# motor_driver.net
KiCad netlist of a schematic drawn in Altium Designer
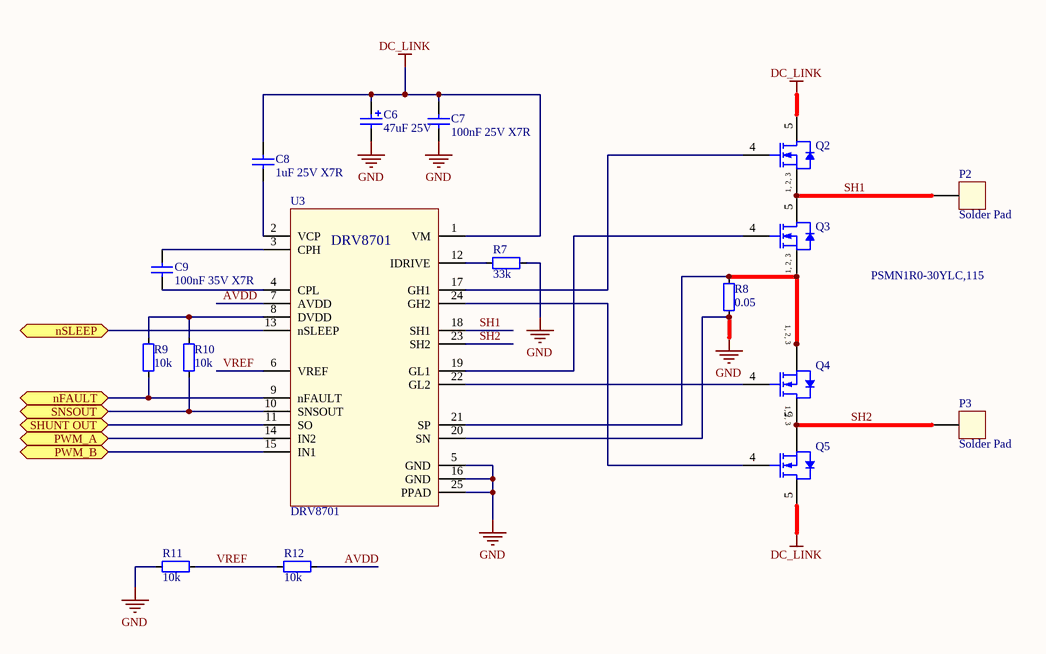
[diagram p0: motor driver.SchDoc]

(export (version "E")
  (design (tool "Eeschema 10.0.6"))
  (components
    (comp (ref "C6")
      (value "47uF 25V")
      (footprint "ELECTROLYTIC 5mm")
      (description "Electrolytic capacitor")
      (libsource (lib "Capacitors") (part "Electrolytic"))
    )
    (comp (ref "C7")
      (value "100nF 25V X7R")
      (footprint "CAP_0603")
      (description "AEC Ceramic capacitor X7R")
      (libsource (lib "Capacitors") (part "Ceramic"))
    )
    (comp (ref "C8")
      (value "1uF 25V X7R")
      (footprint "CAP_0603")
      (description "AEC Ceramic capacitor X7R")
      (libsource (lib "Capacitors") (part "Ceramic"))
    )
    (comp (ref "C9")
      (value "100nF 35V X7R")
      (footprint "CAP_0603")
      (description "AEC Ceramic capacitor X7R")
      (libsource (lib "Capacitors") (part "Ceramic"))
    )
    (comp (ref "P2")
      (value "Solder Pad")
      (footprint "Solder Pad 6x8")
      (libsource (lib "Connectors") (part "Solder Pad"))
    )
    (comp (ref "P3")
      (value "Solder Pad")
      (footprint "Solder Pad 6x8")
      (libsource (lib "Connectors") (part "Solder Pad"))
    )
    (comp (ref "Q2")
      (value "PSMN1R0-30YLC,115")
      (footprint "NXP-SOT669_N")
      (description "N-Channel Logic Level MOSFET Using NextPower Technology, 30 V, 100 A, 5-Pin SOT669, Tape and Reel")
      (fields (field (name "MANUFACTURER") "NXP Semiconductors"))
      (libsource (lib "NXP Semiconductors Standard MOSFETs") (part "PSMN1R0-30YLC,115"))
    )
    (comp (ref "Q3")
      (value "PSMN1R0-30YLC,115")
      (footprint "NXP-SOT669_N")
      (description "N-Channel Logic Level MOSFET Using NextPower Technology, 30 V, 100 A, 5-Pin SOT669, Tape and Reel")
      (fields (field (name "MANUFACTURER") "NXP Semiconductors"))
      (libsource (lib "NXP Semiconductors Standard MOSFETs") (part "PSMN1R0-30YLC,115"))
    )
    (comp (ref "Q4")
      (value "PSMN1R0-30YLC,115")
      (footprint "NXP-SOT669_N")
      (description "N-Channel Logic Level MOSFET Using NextPower Technology, 30 V, 100 A, 5-Pin SOT669, Tape and Reel")
      (fields (field (name "MANUFACTURER") "NXP Semiconductors"))
      (libsource (lib "NXP Semiconductors Standard MOSFETs") (part "PSMN1R0-30YLC,115"))
    )
    (comp (ref "Q5")
      (value "PSMN1R0-30YLC,115")
      (footprint "NXP-SOT669_N")
      (description "N-Channel Logic Level MOSFET Using NextPower Technology, 30 V, 100 A, 5-Pin SOT669, Tape and Reel")
      (fields (field (name "MANUFACTURER") "NXP Semiconductors"))
      (libsource (lib "NXP Semiconductors Standard MOSFETs") (part "PSMN1R0-30YLC,115"))
    )
    (comp (ref "R7")
      (value "33k")
      (footprint "RES_0603")
      (description "Default resistor")
      (libsource (lib "") (part "Resistor_2"))
    )
    (comp (ref "R8")
      (value "0.05")
      (footprint "CSS2H-2512")
      (description "AEC 500uOm 6W precision current sense resistor")
      (fields (field (name "PART_NUMBER") "CSS2H-2512R-L500F"))
      (libsource (lib "Resistors") (part "CSS2H-2512R-L500F"))
    )
    (comp (ref "R9")
      (value "10k")
      (footprint "RES_0603")
      (description "Default resistor")
      (libsource (lib "Resistors") (part "Resistor"))
    )
    (comp (ref "R10")
      (value "10k")
      (footprint "RES_0603")
      (description "Default resistor")
      (libsource (lib "Resistors") (part "Resistor"))
    )
    (comp (ref "R11")
      (value "10k")
      (footprint "RES_0603")
      (description "Default resistor")
      (libsource (lib "") (part "Resistor_1"))
    )
    (comp (ref "R12")
      (value "10k")
      (footprint "RES_0603")
      (description "Default resistor")
      (libsource (lib "") (part "Resistor_1"))
    )
    (comp (ref "U3")
      (value "DRV8701")
      (footprint "VQFN24")
      (libsource (lib "Texas_Instruments") (part "DRV8701"))
    )
  )
  (nets
    (net (code "1") (name "/AVDD") (class "Default")
      (node (ref "R12") (pin "1") (pinfunction "1_1") (pintype "passive"))
      (node (ref "U3") (pin "7") (pinfunction "AVDD_7") (pintype "passive"))
    )
    (net (code "2") (name "/PWM_A") (class "Default")
      (node (ref "U3") (pin "14") (pinfunction "IN2_14") (pintype "passive"))
    )
    (net (code "3") (name "/PWM_B") (class "Default")
      (node (ref "U3") (pin "15") (pinfunction "IN1_15") (pintype "passive"))
    )
    (net (code "4") (name "/SH1") (class "Default")
      (node (ref "P2") (pin "1") (pinfunction "1_1") (pintype "passive"))
      (node (ref "Q2") (pin "1") (pinfunction "S_1") (pintype "passive"))
      (node (ref "Q2") (pin "2") (pinfunction "S_2") (pintype "passive"))
      (node (ref "Q2") (pin "3") (pinfunction "S_3") (pintype "passive"))
      (node (ref "Q3") (pin "5") (pinfunction "D_5") (pintype "passive"))
      (node (ref "U3") (pin "18") (pinfunction "SH1_18") (pintype "passive"))
    )
    (net (code "5") (name "/SH2") (class "Default")
      (node (ref "P3") (pin "1") (pinfunction "1_1") (pintype "passive"))
      (node (ref "Q4") (pin "5") (pinfunction "D_5") (pintype "passive"))
      (node (ref "Q5") (pin "1") (pinfunction "S_1") (pintype "passive"))
      (node (ref "Q5") (pin "2") (pinfunction "S_2") (pintype "passive"))
      (node (ref "Q5") (pin "3") (pinfunction "S_3") (pintype "passive"))
      (node (ref "U3") (pin "23") (pinfunction "SH2_23") (pintype "passive"))
    )
    (net (code "6") (name "/SHUNT OUT") (class "Default")
      (node (ref "U3") (pin "11") (pinfunction "SO_11") (pintype "passive"))
    )
    (net (code "7") (name "/SNSOUT") (class "Default")
      (node (ref "R10") (pin "1") (pinfunction "1_1") (pintype "passive"))
      (node (ref "U3") (pin "10") (pinfunction "SNSOUT_10") (pintype "passive"))
    )
    (net (code "8") (name "/VREF") (class "Default")
      (node (ref "R11") (pin "1") (pinfunction "1_1") (pintype "passive"))
      (node (ref "R12") (pin "2") (pinfunction "2_2") (pintype "passive"))
      (node (ref "U3") (pin "6") (pinfunction "VREF_6") (pintype "passive"))
    )
    (net (code "9") (name "/nFAULT") (class "Default")
      (node (ref "R9") (pin "1") (pinfunction "1_1") (pintype "passive"))
      (node (ref "U3") (pin "9") (pinfunction "nFAULT_9") (pintype "passive"))
    )
    (net (code "10") (name "/nSLEEP") (class "Default")
      (node (ref "U3") (pin "13") (pinfunction "nSLEEP_13") (pintype "passive"))
    )
    (net (code "11") (name "DC_LINK") (class "Default")
      (node (ref "C6") (pin "1") (pinfunction "1_1") (pintype "passive"))
      (node (ref "C7") (pin "2") (pinfunction "2_2") (pintype "passive"))
      (node (ref "C8") (pin "2") (pinfunction "2_2") (pintype "passive"))
      (node (ref "Q2") (pin "5") (pinfunction "D_5") (pintype "passive"))
      (node (ref "Q5") (pin "5") (pinfunction "D_5") (pintype "passive"))
      (node (ref "U3") (pin "1") (pinfunction "VM_1") (pintype "passive"))
    )
    (net (code "12") (name "GND") (class "Default")
      (node (ref "C6") (pin "2") (pinfunction "2_2") (pintype "passive"))
      (node (ref "C7") (pin "1") (pinfunction "1_1") (pintype "passive"))
      (node (ref "R11") (pin "2") (pinfunction "2_2") (pintype "passive"))
      (node (ref "R7") (pin "2") (pinfunction "2_2") (pintype "passive"))
      (node (ref "R8") (pin "1") (pinfunction "1_1") (pintype "passive"))
      (node (ref "U3") (pin "16") (pinfunction "GND_16") (pintype "passive"))
      (node (ref "U3") (pin "20") (pinfunction "SN_20") (pintype "passive"))
      (node (ref "U3") (pin "25") (pinfunction "PPAD_25") (pintype "passive"))
      (node (ref "U3") (pin "5") (pinfunction "GND_5") (pintype "passive"))
    )
    (net (code "13") (name "Net-(Q2-G)") (class "Default")
      (node (ref "Q2") (pin "4") (pinfunction "G_4") (pintype "passive"))
      (node (ref "U3") (pin "17") (pinfunction "GH1_17") (pintype "passive"))
    )
    (net (code "14") (name "Net-(Q3-G)") (class "Default")
      (node (ref "Q3") (pin "4") (pinfunction "G_4") (pintype "passive"))
      (node (ref "U3") (pin "19") (pinfunction "GL1_19") (pintype "passive"))
    )
    (net (code "15") (name "Net-(Q4-G)") (class "Default")
      (node (ref "Q4") (pin "4") (pinfunction "G_4") (pintype "passive"))
      (node (ref "U3") (pin "22") (pinfunction "GL2_22") (pintype "passive"))
    )
    (net (code "16") (name "Net-(Q5-G)") (class "Default")
      (node (ref "Q5") (pin "4") (pinfunction "G_4") (pintype "passive"))
      (node (ref "U3") (pin "24") (pinfunction "GH2_24") (pintype "passive"))
    )
    (net (code "17") (name "Net-(U3-CPH)") (class "Default")
      (node (ref "C9") (pin "2") (pinfunction "2_2") (pintype "passive"))
      (node (ref "U3") (pin "3") (pinfunction "CPH_3") (pintype "passive"))
    )
    (net (code "18") (name "Net-(U3-CPL)") (class "Default")
      (node (ref "C9") (pin "1") (pinfunction "1_1") (pintype "passive"))
      (node (ref "U3") (pin "4") (pinfunction "CPL_4") (pintype "passive"))
    )
    (net (code "19") (name "Net-(U3-DVDD)") (class "Default")
      (node (ref "R10") (pin "2") (pinfunction "2_2") (pintype "passive"))
      (node (ref "R9") (pin "2") (pinfunction "2_2") (pintype "passive"))
      (node (ref "U3") (pin "8") (pinfunction "DVDD_8") (pintype "passive"))
    )
    (net (code "20") (name "Net-(U3-IDRIVE)") (class "Default")
      (node (ref "R7") (pin "1") (pinfunction "1_1") (pintype "passive"))
      (node (ref "U3") (pin "12") (pinfunction "IDRIVE_12") (pintype "passive"))
    )
    (net (code "21") (name "Net-(U3-SP)") (class "Default")
      (node (ref "Q3") (pin "1") (pinfunction "S_1") (pintype "passive"))
      (node (ref "Q3") (pin "2") (pinfunction "S_2") (pintype "passive"))
      (node (ref "Q3") (pin "3") (pinfunction "S_3") (pintype "passive"))
      (node (ref "Q4") (pin "1") (pinfunction "S_1") (pintype "passive"))
      (node (ref "Q4") (pin "2") (pinfunction "S_2") (pintype "passive"))
      (node (ref "Q4") (pin "3") (pinfunction "S_3") (pintype "passive"))
      (node (ref "R8") (pin "2") (pinfunction "2_2") (pintype "passive"))
      (node (ref "U3") (pin "21") (pinfunction "SP_21") (pintype "passive"))
    )
    (net (code "22") (name "Net-(U3-VCP)") (class "Default")
      (node (ref "C8") (pin "1") (pinfunction "1_1") (pintype "passive"))
      (node (ref "U3") (pin "2") (pinfunction "VCP_2") (pintype "passive"))
    )
  )
)
